# schematic.net
KiCad netlist of a schematic drawn in EAGLE
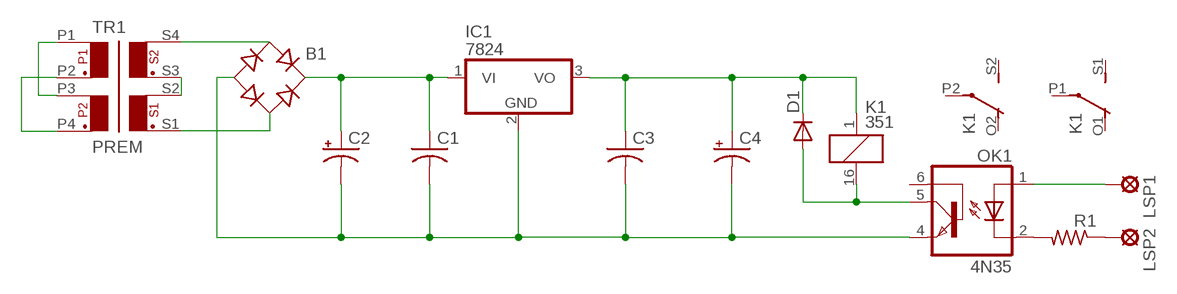
[diagram p0: schematic, sheet 1]

(export (version "E")
  (design (tool "Eeschema 10.0.6"))
  (components
    (comp (ref "B1")
      (value "B-DIL")
      (footprint "eagle-import:B-DIL")
      (libsource (lib "eagle-import") (part "B-DIL"))
    )
    (comp (ref "C1")
      (value "C-US025-024X044")
      (footprint "eagle-import:C025-024X044")
      (libsource (lib "eagle-import") (part "C-US025-024X044"))
    )
    (comp (ref "C2")
      (value "CPOL-USE5-8.5")
      (footprint "eagle-import:E5-8,5")
      (libsource (lib "eagle-import") (part "CPOL-USE5-8.5"))
    )
    (comp (ref "C3")
      (value "C-US025-024X044")
      (footprint "eagle-import:C025-024X044")
      (libsource (lib "eagle-import") (part "C-US025-024X044"))
    )
    (comp (ref "C4")
      (value "CPOL-USE2.5-7")
      (footprint "eagle-import:E2,5-7")
      (libsource (lib "eagle-import") (part "CPOL-USE2.5-7"))
    )
    (comp (ref "D1")
      (value "1N4148DO35-7")
      (footprint "eagle-import:DO35-7")
      (libsource (lib "eagle-import") (part "1N4148DO35-7"))
    )
    (comp (ref "IC1")
      (value "7824")
      (footprint "eagle-import:TO220H")
      (libsource (lib "eagle-import") (part "78T24"))
    )
    (comp (ref "K1")
      (value "351")
      (footprint "eagle-import:351")
      (libsource (lib "eagle-import") (part "351"))
    )
    (comp (ref "LSP1")
      (value "LSP10")
      (footprint "eagle-import:LSP10")
      (libsource (lib "eagle-import") (part "LSP10"))
    )
    (comp (ref "LSP2")
      (value "LSP10")
      (footprint "eagle-import:LSP10")
      (libsource (lib "eagle-import") (part "LSP10"))
    )
    (comp (ref "OK1")
      (value "4N35")
      (footprint "eagle-import:DIL06")
      (fields (field (name "MF") "FAIRCHILD SEMICONDUCTOR"))
      (libsource (lib "eagle-import") (part "4N35"))
    )
    (comp (ref "R1")
      (value "R-US_0204/2V")
      (footprint "eagle-import:0204V")
      (libsource (lib "eagle-import") (part "R-US_0204/2V"))
    )
    (comp (ref "TR1")
      (value "PREM")
      (footprint "eagle-import:PREM-2P2S")
      (libsource (lib "eagle-import") (part "PREM"))
    )
  )
  (nets
    (net (code "1") (name "Net-(B1-PadAC1)") (class "Default")
      (node (ref "B1") (pin "AC1") (pinfunction "AC1_AC1") (pintype "passive"))
      (node (ref "TR1") (pin "S4") (pinfunction "S4_S4") (pintype "passive"))
    )
    (net (code "2") (name "Net-(B1-PadAC2)") (class "Default")
      (node (ref "B1") (pin "AC2") (pinfunction "AC2_AC2") (pintype "passive"))
      (node (ref "TR1") (pin "S1") (pinfunction "S1_S1") (pintype "passive"))
    )
    (net (code "3") (name "Net-(IC1-GND)") (class "Default")
      (node (ref "B1") (pin "-") (pinfunction "-_-") (pintype "passive"))
      (node (ref "C1") (pin "2") (pinfunction "2_2") (pintype "passive"))
      (node (ref "C2") (pin "-") (pinfunction "-_-") (pintype "passive"))
      (node (ref "C3") (pin "2") (pinfunction "2_2") (pintype "passive"))
      (node (ref "C4") (pin "-") (pinfunction "-_-") (pintype "passive"))
      (node (ref "IC1") (pin "2") (pinfunction "GND_2") (pintype "passive"))
      (node (ref "OK1") (pin "4") (pinfunction "EMI_4") (pintype "passive"))
    )
    (net (code "4") (name "Net-(IC1-VI)") (class "Default")
      (node (ref "B1") (pin "+") (pinfunction "+_+") (pintype "passive"))
      (node (ref "C1") (pin "1") (pinfunction "1_1") (pintype "passive"))
      (node (ref "C2") (pin "+") (pinfunction "+_+") (pintype "passive"))
      (node (ref "IC1") (pin "1") (pinfunction "VI_1") (pintype "input"))
    )
    (net (code "5") (name "Net-(IC1-VO)") (class "Default")
      (node (ref "C3") (pin "1") (pinfunction "1_1") (pintype "passive"))
      (node (ref "C4") (pin "+") (pinfunction "+_+") (pintype "passive"))
      (node (ref "D1") (pin "C") (pinfunction "C_C") (pintype "passive"))
      (node (ref "IC1") (pin "3") (pinfunction "VO_3") (pintype "passive"))
      (node (ref "K1") (pin "1") (pinfunction "1_1") (pintype "passive"))
    )
    (net (code "6") (name "Net-(K1A-2)") (class "Default")
      (node (ref "D1") (pin "A") (pinfunction "A_A") (pintype "passive"))
      (node (ref "K1") (pin "16") (pinfunction "2_16") (pintype "passive"))
      (node (ref "OK1") (pin "5") (pinfunction "COL_5") (pintype "passive"))
    )
    (net (code "7") (name "Net-(LSP2-PadMP)") (class "Default")
      (node (ref "LSP2") (pin "MP") (pinfunction "MP_MP") (pintype "passive"))
      (node (ref "R1") (pin "1") (pinfunction "1_1") (pintype "passive"))
    )
    (net (code "8") (name "Net-(OK1-A)") (class "Default")
      (node (ref "LSP1") (pin "MP") (pinfunction "MP_MP") (pintype "passive"))
      (node (ref "OK1") (pin "1") (pinfunction "A_1") (pintype "passive"))
    )
    (net (code "9") (name "Net-(OK1-C)") (class "Default")
      (node (ref "OK1") (pin "2") (pinfunction "C_2") (pintype "passive"))
      (node (ref "R1") (pin "2") (pinfunction "2_2") (pintype "passive"))
    )
    (net (code "10") (name "Net-(TR1-PadP1)") (class "Default")
      (node (ref "TR1") (pin "P1") (pinfunction "P1_P1") (pintype "passive"))
      (node (ref "TR1") (pin "P3") (pinfunction "P3_P3") (pintype "passive"))
    )
    (net (code "11") (name "Net-(TR1-PadP2)") (class "Default")
      (node (ref "TR1") (pin "P2") (pinfunction "P2_P2") (pintype "passive"))
      (node (ref "TR1") (pin "P4") (pinfunction "P4_P4") (pintype "passive"))
    )
    (net (code "12") (name "Net-(TR1-PadS2)") (class "Default")
      (node (ref "TR1") (pin "S2") (pinfunction "S2_S2") (pintype "passive"))
      (node (ref "TR1") (pin "S3") (pinfunction "S3_S3") (pintype "passive"))
    )
    (net (code "13") (name "unconnected-(K1B-O-PadO1)") (class "Default")
      (node (ref "K1") (pin "O1") (pinfunction "O_O1") (pintype "passive"))
    )
    (net (code "14") (name "unconnected-(K1B-P-PadP1)") (class "Default")
      (node (ref "K1") (pin "P1") (pinfunction "P_P1") (pintype "passive"))
    )
    (net (code "15") (name "unconnected-(K1B-S-PadS1)") (class "Default")
      (node (ref "K1") (pin "S1") (pinfunction "S_S1") (pintype "passive"))
    )
    (net (code "16") (name "unconnected-(K1C-O-PadO2)") (class "Default")
      (node (ref "K1") (pin "O2") (pinfunction "O_O2") (pintype "passive"))
    )
    (net (code "17") (name "unconnected-(K1C-P-PadP2)") (class "Default")
      (node (ref "K1") (pin "P2") (pinfunction "P_P2") (pintype "passive"))
    )
    (net (code "18") (name "unconnected-(K1C-S-PadS2)") (class "Default")
      (node (ref "K1") (pin "S2") (pinfunction "S_S2") (pintype "passive"))
    )
    (net (code "19") (name "unconnected-(OK1-BAS-Pad6)") (class "Default")
      (node (ref "OK1") (pin "6") (pinfunction "BAS_6") (pintype "passive"))
    )
  )
)
